# spi-devices.net
KiCad netlist of a schematic drawn in EAGLE
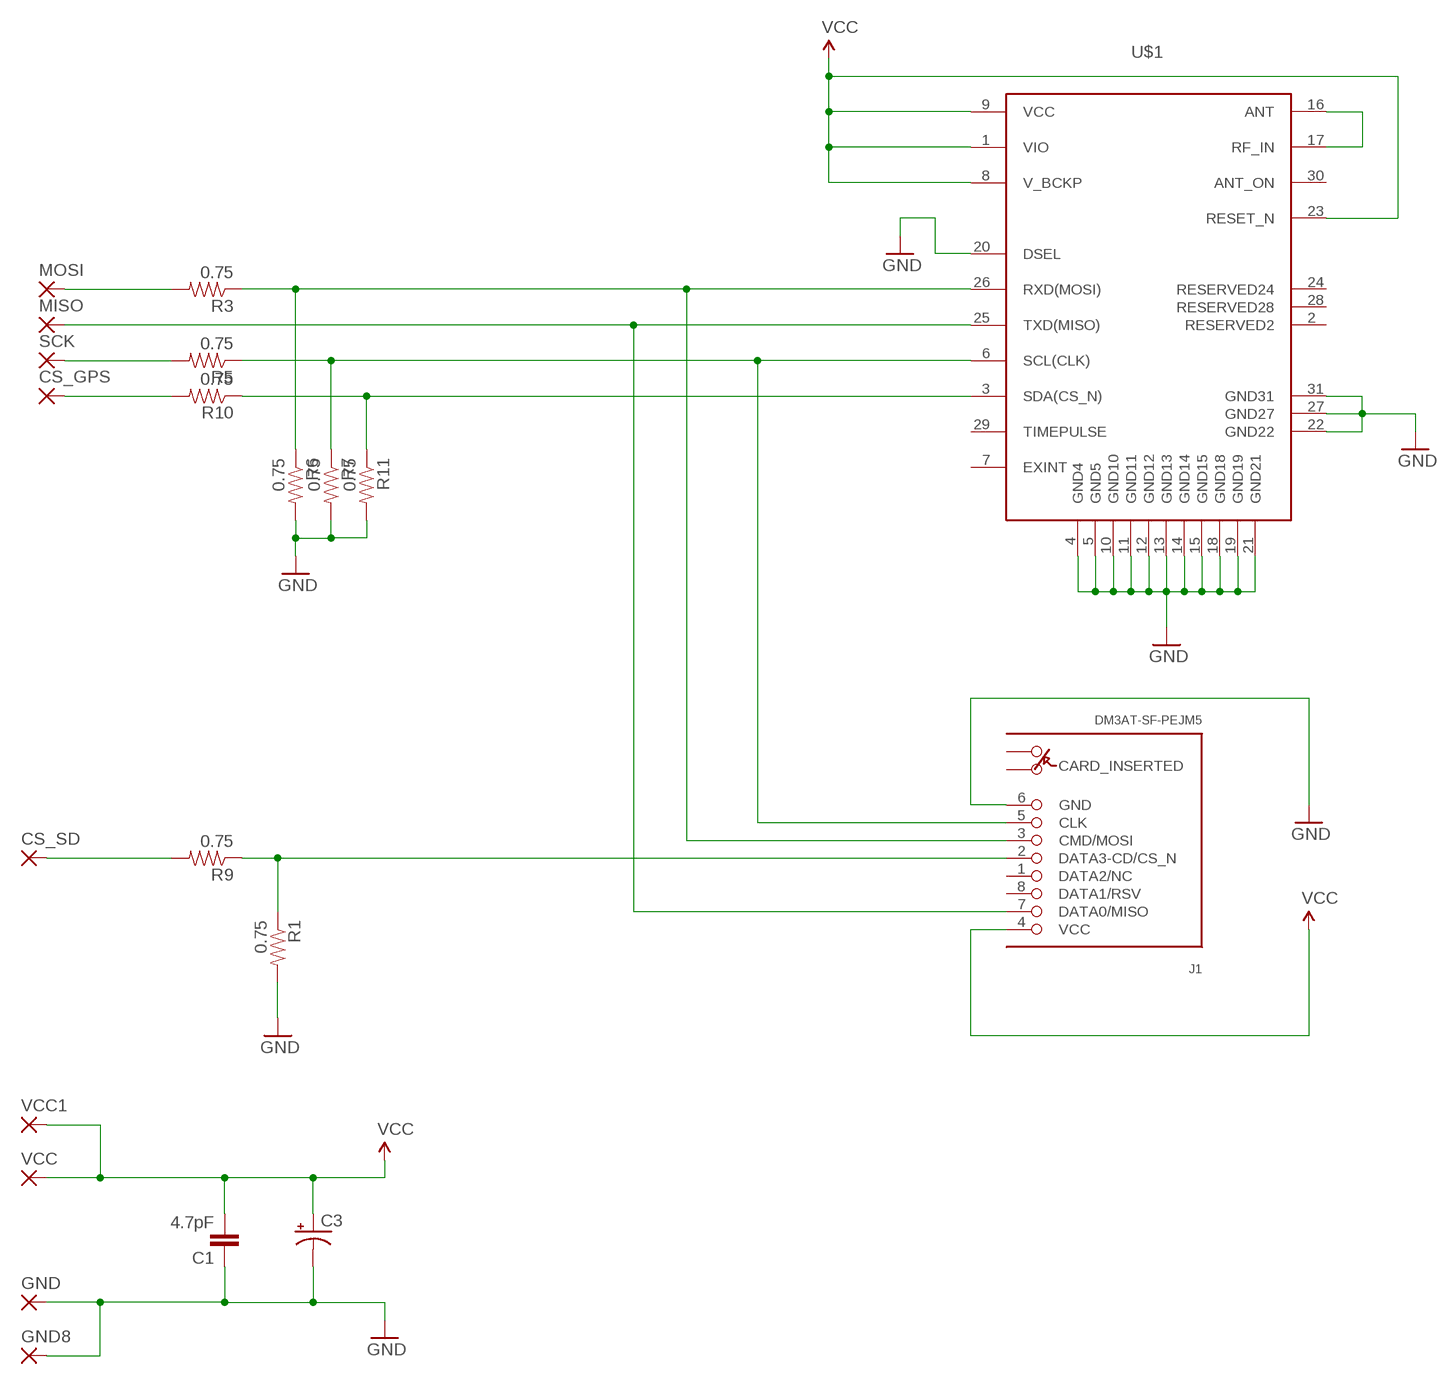
[diagram p0: schematic, sheet 1]

(export (version "E")
  (design (tool "Eeschema 10.0.6"))
  (components
    (comp (ref "C1")
      (value "4.7pF")
      (footprint "eagle-import:C0603")
      (libsource (lib "eagle-import") (part "C-EUC0603"))
    )
    (comp (ref "C3")
      (value "CAP_POL3528")
      (footprint "eagle-import:EIA3528")
      (libsource (lib "eagle-import") (part "CAP_POL3528"))
    )
    (comp (ref "CS_GPS")
      (value "2,54/0,9")
      (footprint "eagle-import:2,54_0,9")
      (libsource (lib "eagle-import") (part "2,54/0,9"))
    )
    (comp (ref "CS_SD")
      (value "2,54/0,9")
      (footprint "eagle-import:2,54_0,9")
      (libsource (lib "eagle-import") (part "2,54/0,9"))
    )
    (comp (ref "GND")
      (value "2,54/0,9")
      (footprint "eagle-import:2,54_0,9")
      (libsource (lib "eagle-import") (part "2,54/0,9"))
    )
    (comp (ref "GND8")
      (value "2,54/0,9")
      (footprint "eagle-import:2,54_0,9")
      (libsource (lib "eagle-import") (part "2,54/0,9"))
    )
    (comp (ref "J1")
      (value "DM3AT-SF-PEJM5")
      (footprint "eagle-import:DM3AT-SF-PEJM5")
      (libsource (lib "eagle-import") (part "DM3AT-SF-PEJM5"))
    )
    (comp (ref "MISO")
      (value "2,54/0,9")
      (footprint "eagle-import:2,54_0,9")
      (libsource (lib "eagle-import") (part "2,54/0,9"))
    )
    (comp (ref "MOSI")
      (value "2,54/0,9")
      (footprint "eagle-import:2,54_0,9")
      (libsource (lib "eagle-import") (part "2,54/0,9"))
    )
    (comp (ref "R1")
      (value "0.75")
      (footprint "eagle-import:0805")
      (libsource (lib "eagle-import") (part "0.75OHM-1/4W-1%(0805)"))
    )
    (comp (ref "R3")
      (value "0.75")
      (footprint "eagle-import:0805")
      (libsource (lib "eagle-import") (part "0.75OHM-1/4W-1%(0805)"))
    )
    (comp (ref "R5")
      (value "0.75")
      (footprint "eagle-import:0805")
      (libsource (lib "eagle-import") (part "0.75OHM-1/4W-1%(0805)"))
    )
    (comp (ref "R6")
      (value "0.75")
      (footprint "eagle-import:0805")
      (libsource (lib "eagle-import") (part "0.75OHM-1/4W-1%(0805)"))
    )
    (comp (ref "R7")
      (value "0.75")
      (footprint "eagle-import:0805")
      (libsource (lib "eagle-import") (part "0.75OHM-1/4W-1%(0805)"))
    )
    (comp (ref "R9")
      (value "0.75")
      (footprint "eagle-import:0805")
      (libsource (lib "eagle-import") (part "0.75OHM-1/4W-1%(0805)"))
    )
    (comp (ref "R10")
      (value "0.75")
      (footprint "eagle-import:0805")
      (libsource (lib "eagle-import") (part "0.75OHM-1/4W-1%(0805)"))
    )
    (comp (ref "R11")
      (value "0.75")
      (footprint "eagle-import:0805")
      (libsource (lib "eagle-import") (part "0.75OHM-1/4W-1%(0805)"))
    )
    (comp (ref "SCK")
      (value "2,54/0,9")
      (footprint "eagle-import:2,54_0,9")
      (libsource (lib "eagle-import") (part "2,54/0,9"))
    )
    (comp (ref "U$1")
      (value "CAM-M8Q")
      (footprint "eagle-import:CAM-M8Q")
      (libsource (lib "eagle-import") (part "CAM-M8Q"))
    )
    (comp (ref "VCC")
      (value "2,54/0,9")
      (footprint "eagle-import:2,54_0,9")
      (libsource (lib "eagle-import") (part "2,54/0,9"))
    )
    (comp (ref "VCC1")
      (value "2,54/0,9")
      (footprint "eagle-import:2,54_0,9")
      (libsource (lib "eagle-import") (part "2,54/0,9"))
    )
  )
  (nets
    (net (code "1") (name "GND") (class "Default")
      (node (ref "C1") (pin "1") (pinfunction "1_1") (pintype "passive"))
      (node (ref "C3") (pin "C") (pinfunction "-_C") (pintype "passive"))
      (node (ref "GND") (pin "1") (pinfunction "P_1") (pintype "passive"))
      (node (ref "GND8") (pin "1") (pinfunction "P_1") (pintype "passive"))
      (node (ref "J1") (pin "6") (pinfunction "GND_6") (pintype "bidirectional"))
      (node (ref "R1") (pin "2") (pinfunction "2_2") (pintype "passive"))
      (node (ref "R11") (pin "2") (pinfunction "2_2") (pintype "passive"))
      (node (ref "R6") (pin "2") (pinfunction "2_2") (pintype "passive"))
      (node (ref "R7") (pin "2") (pinfunction "2_2") (pintype "passive"))
      (node (ref "U$1") (pin "10") (pinfunction "GND10_10") (pintype "bidirectional"))
      (node (ref "U$1") (pin "11") (pinfunction "GND11_11") (pintype "bidirectional"))
      (node (ref "U$1") (pin "12") (pinfunction "GND12_12") (pintype "bidirectional"))
      (node (ref "U$1") (pin "13") (pinfunction "GND13_13") (pintype "bidirectional"))
      (node (ref "U$1") (pin "14") (pinfunction "GND14_14") (pintype "bidirectional"))
      (node (ref "U$1") (pin "15") (pinfunction "GND15_15") (pintype "bidirectional"))
      (node (ref "U$1") (pin "18") (pinfunction "GND18_18") (pintype "bidirectional"))
      (node (ref "U$1") (pin "19") (pinfunction "GND19_19") (pintype "bidirectional"))
      (node (ref "U$1") (pin "20") (pinfunction "DSEL_20") (pintype "bidirectional"))
      (node (ref "U$1") (pin "21") (pinfunction "GND21_21") (pintype "bidirectional"))
      (node (ref "U$1") (pin "22") (pinfunction "GND22_22") (pintype "bidirectional"))
      (node (ref "U$1") (pin "27") (pinfunction "GND27_27") (pintype "bidirectional"))
      (node (ref "U$1") (pin "31") (pinfunction "GND31_31") (pintype "bidirectional"))
      (node (ref "U$1") (pin "4") (pinfunction "GND4_4") (pintype "bidirectional"))
      (node (ref "U$1") (pin "5") (pinfunction "GND5_5") (pintype "bidirectional"))
    )
    (net (code "2") (name "Net-(CS_GPS-P)") (class "Default")
      (node (ref "CS_GPS") (pin "1") (pinfunction "P_1") (pintype "passive"))
      (node (ref "R10") (pin "2") (pinfunction "2_2") (pintype "passive"))
    )
    (net (code "3") (name "Net-(CS_SD-P)") (class "Default")
      (node (ref "CS_SD") (pin "1") (pinfunction "P_1") (pintype "passive"))
      (node (ref "R9") (pin "2") (pinfunction "2_2") (pintype "passive"))
    )
    (net (code "4") (name "Net-(J1-CLK)") (class "Default")
      (node (ref "J1") (pin "5") (pinfunction "CLK_5") (pintype "bidirectional"))
      (node (ref "R5") (pin "1") (pinfunction "1_1") (pintype "passive"))
      (node (ref "R7") (pin "1") (pinfunction "1_1") (pintype "passive"))
      (node (ref "U$1") (pin "6") (pinfunction "SCL(CLK)_6") (pintype "bidirectional"))
    )
    (net (code "5") (name "Net-(J1-CMD{slash}MOSI)") (class "Default")
      (node (ref "J1") (pin "3") (pinfunction "CMD/MOSI_3") (pintype "bidirectional"))
      (node (ref "R3") (pin "1") (pinfunction "1_1") (pintype "passive"))
      (node (ref "R6") (pin "1") (pinfunction "1_1") (pintype "passive"))
      (node (ref "U$1") (pin "26") (pinfunction "RXD(MOSI)_26") (pintype "bidirectional"))
    )
    (net (code "6") (name "Net-(J1-DATA0{slash}MISO)") (class "Default")
      (node (ref "J1") (pin "7") (pinfunction "DATA0/MISO_7") (pintype "bidirectional"))
      (node (ref "MISO") (pin "1") (pinfunction "P_1") (pintype "passive"))
      (node (ref "U$1") (pin "25") (pinfunction "TXD(MISO)_25") (pintype "bidirectional"))
    )
    (net (code "7") (name "Net-(J1-DATA3-CD{slash}CS_N)") (class "Default")
      (node (ref "J1") (pin "2") (pinfunction "DATA3-CD/CS_N_2") (pintype "bidirectional"))
      (node (ref "R1") (pin "1") (pinfunction "1_1") (pintype "passive"))
      (node (ref "R9") (pin "1") (pinfunction "1_1") (pintype "passive"))
    )
    (net (code "8") (name "Net-(MOSI-P)") (class "Default")
      (node (ref "MOSI") (pin "1") (pinfunction "P_1") (pintype "passive"))
      (node (ref "R3") (pin "2") (pinfunction "2_2") (pintype "passive"))
    )
    (net (code "9") (name "Net-(SCK-P)") (class "Default")
      (node (ref "R5") (pin "2") (pinfunction "2_2") (pintype "passive"))
      (node (ref "SCK") (pin "1") (pinfunction "P_1") (pintype "passive"))
    )
    (net (code "10") (name "Net-(U$1-ANT)") (class "Default")
      (node (ref "U$1") (pin "16") (pinfunction "ANT_16") (pintype "bidirectional"))
      (node (ref "U$1") (pin "17") (pinfunction "RF_IN_17") (pintype "bidirectional"))
    )
    (net (code "11") (name "Net-(U$1-SDA(CS_N))") (class "Default")
      (node (ref "R10") (pin "1") (pinfunction "1_1") (pintype "passive"))
      (node (ref "R11") (pin "1") (pinfunction "1_1") (pintype "passive"))
      (node (ref "U$1") (pin "3") (pinfunction "SDA(CS_N)_3") (pintype "bidirectional"))
    )
    (net (code "12") (name "VCC") (class "Default")
      (node (ref "C1") (pin "2") (pinfunction "2_2") (pintype "passive"))
      (node (ref "C3") (pin "A") (pinfunction "+_A") (pintype "passive"))
      (node (ref "J1") (pin "4") (pinfunction "VCC_4") (pintype "bidirectional"))
      (node (ref "U$1") (pin "1") (pinfunction "VIO_1") (pintype "bidirectional"))
      (node (ref "U$1") (pin "23") (pinfunction "RESET_N_23") (pintype "bidirectional"))
      (node (ref "U$1") (pin "8") (pinfunction "V_BCKP_8") (pintype "bidirectional"))
      (node (ref "U$1") (pin "9") (pinfunction "VCC_9") (pintype "bidirectional"))
      (node (ref "VCC") (pin "1") (pinfunction "P_1") (pintype "passive"))
      (node (ref "VCC1") (pin "1") (pinfunction "P_1") (pintype "passive"))
    )
    (net (code "13") (name "unconnected-(J1-DATA1{slash}RSV-Pad8)") (class "Default")
      (node (ref "J1") (pin "8") (pinfunction "DATA1/RSV_8") (pintype "bidirectional"))
    )
    (net (code "14") (name "unconnected-(J1-DATA2{slash}NC-Pad1)") (class "Default")
      (node (ref "J1") (pin "1") (pinfunction "DATA2/NC_1") (pintype "bidirectional"))
    )
    (net (code "15") (name "unconnected-(J1-PadA)") (class "Default")
      (node (ref "J1") (pin "A") (pinfunction "A_A") (pintype "bidirectional"))
    )
    (net (code "16") (name "unconnected-(J1-PadB)") (class "Default")
      (node (ref "J1") (pin "B") (pinfunction "B_B") (pintype "bidirectional"))
    )
    (net (code "17") (name "unconnected-(U$1-ANT_ON-Pad30)") (class "Default")
      (node (ref "U$1") (pin "30") (pinfunction "ANT_ON_30") (pintype "bidirectional"))
    )
    (net (code "18") (name "unconnected-(U$1-EXINT-Pad7)") (class "Default")
      (node (ref "U$1") (pin "7") (pinfunction "EXINT_7") (pintype "bidirectional"))
    )
    (net (code "19") (name "unconnected-(U$1-RESERVED2-Pad2)") (class "Default")
      (node (ref "U$1") (pin "2") (pinfunction "RESERVED2_2") (pintype "bidirectional"))
    )
    (net (code "20") (name "unconnected-(U$1-RESERVED24-Pad24)") (class "Default")
      (node (ref "U$1") (pin "24") (pinfunction "RESERVED24_24") (pintype "bidirectional"))
    )
    (net (code "21") (name "unconnected-(U$1-RESERVED28-Pad28)") (class "Default")
      (node (ref "U$1") (pin "28") (pinfunction "RESERVED28_28") (pintype "bidirectional"))
    )
    (net (code "22") (name "unconnected-(U$1-TIMEPULSE-Pad29)") (class "Default")
      (node (ref "U$1") (pin "29") (pinfunction "TIMEPULSE_29") (pintype "bidirectional"))
    )
  )
)
